# MegaD-328_7I7O_Shematic.net
KiCad netlist of a schematic drawn in Altium Designer
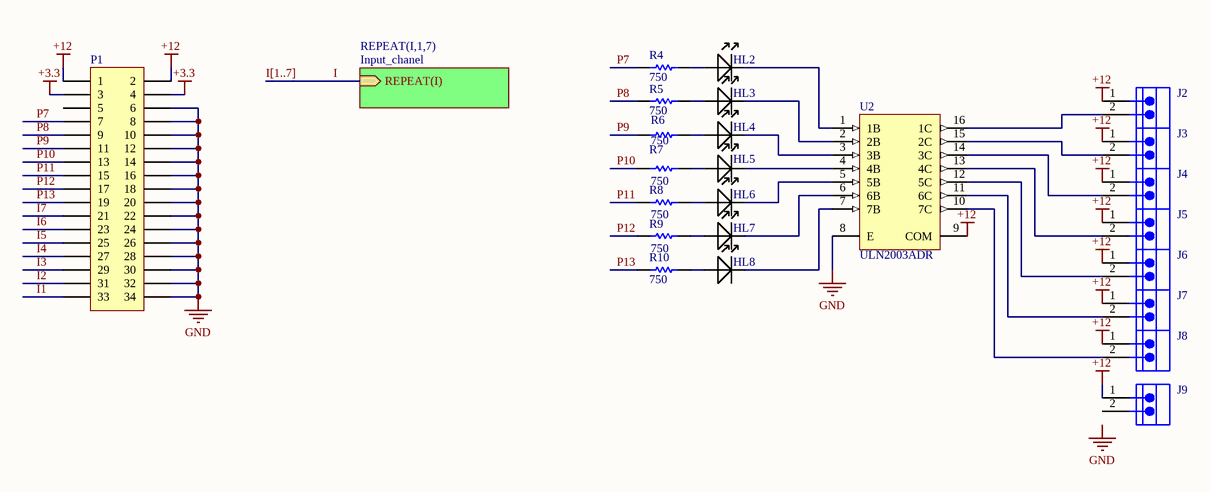
[diagram p0: MegaD-328_7I7O_Shematic.SchDoc]

(export (version "E")
  (design (tool "Eeschema 10.0.6"))
  (components
    (comp (ref "HL2")
      (value "LED_SMD")
      (footprint "0805_LED")
      (description "0805 led")
      (libsource (lib "altium-import") (part "root_0_LED_SMD_"))
    )
    (comp (ref "HL3")
      (value "LED_SMD")
      (footprint "0805_LED")
      (description "0805 led")
      (libsource (lib "altium-import") (part "root_0_LED_SMD_"))
    )
    (comp (ref "HL4")
      (value "LED_SMD")
      (footprint "0805_LED")
      (description "0805 led")
      (libsource (lib "altium-import") (part "root_0_LED_SMD_"))
    )
    (comp (ref "HL5")
      (value "LED_SMD")
      (footprint "0805_LED")
      (description "0805 led")
      (libsource (lib "altium-import") (part "root_0_LED_SMD_"))
    )
    (comp (ref "HL6")
      (value "LED_SMD")
      (footprint "0805_LED")
      (description "0805 led")
      (libsource (lib "altium-import") (part "root_0_LED_SMD_"))
    )
    (comp (ref "HL7")
      (value "LED_SMD")
      (footprint "0805_LED")
      (description "0805 led")
      (libsource (lib "altium-import") (part "root_0_LED_SMD_"))
    )
    (comp (ref "HL8")
      (value "LED_SMD")
      (footprint "0805_LED")
      (description "0805 led")
      (libsource (lib "altium-import") (part "root_0_LED_SMD_"))
    )
    (comp (ref "J2")
      (value "~")
      (footprint "DG301-5.0-02P-1X")
      (fields
        (field (name "MANUFACTURER") "Cixi KaiFeng")
        (field (name "PARTNUMBER") "KF120-02P-14")
        (field (name "CONTACT") "Brass")
      )
      (libsource (lib "altium-import") (part "root_3_Terminal_2_"))
    )
    (comp (ref "J3")
      (value "~")
      (footprint "DG301-5.0-02P-1X")
      (fields
        (field (name "MANUFACTURER") "Cixi KaiFeng")
        (field (name "PARTNUMBER") "KF120-02P-14")
        (field (name "CONTACT") "Brass")
      )
      (libsource (lib "altium-import") (part "root_3_Terminal_2_"))
    )
    (comp (ref "J4")
      (value "~")
      (footprint "DG301-5.0-02P-1X")
      (fields
        (field (name "MANUFACTURER") "Cixi KaiFeng")
        (field (name "PARTNUMBER") "KF120-02P-14")
        (field (name "CONTACT") "Brass")
      )
      (libsource (lib "altium-import") (part "root_3_Terminal_2_"))
    )
    (comp (ref "J5")
      (value "~")
      (footprint "DG301-5.0-02P-1X")
      (fields
        (field (name "MANUFACTURER") "Cixi KaiFeng")
        (field (name "PARTNUMBER") "KF120-02P-14")
        (field (name "CONTACT") "Brass")
      )
      (libsource (lib "altium-import") (part "root_3_Terminal_2_"))
    )
    (comp (ref "J6")
      (value "~")
      (footprint "DG301-5.0-02P-1X")
      (fields
        (field (name "MANUFACTURER") "Cixi KaiFeng")
        (field (name "PARTNUMBER") "KF120-02P-14")
        (field (name "CONTACT") "Brass")
      )
      (libsource (lib "altium-import") (part "root_3_Terminal_2_"))
    )
    (comp (ref "J7")
      (value "~")
      (footprint "DG301-5.0-02P-1X")
      (fields
        (field (name "MANUFACTURER") "Cixi KaiFeng")
        (field (name "PARTNUMBER") "KF120-02P-14")
        (field (name "CONTACT") "Brass")
      )
      (libsource (lib "altium-import") (part "root_3_Terminal_2_"))
    )
    (comp (ref "J8")
      (value "~")
      (footprint "DG301-5.0-02P-1X")
      (fields
        (field (name "MANUFACTURER") "Cixi KaiFeng")
        (field (name "PARTNUMBER") "KF120-02P-14")
        (field (name "CONTACT") "Brass")
      )
      (libsource (lib "altium-import") (part "root_3_Terminal_2_"))
    )
    (comp (ref "J9")
      (value "~")
      (footprint "DG301-5.0-02P-1X")
      (fields
        (field (name "MANUFACTURER") "Cixi KaiFeng")
        (field (name "PARTNUMBER") "KF120-02P-14")
        (field (name "CONTACT") "Brass")
      )
      (libsource (lib "altium-import") (part "root_3_Terminal_2_"))
    )
    (comp (ref "P1")
      (value "~")
      (footprint "HDR2X17-PLC")
      (description "Header, 17-Pin, Dual row")
      (fields (field (name "PUBLISHER") "Altium Limited"))
      (libsource (lib "web.skorpio") (part "Header 17X2"))
    )
    (comp (ref "R4")
      (value "RES_SMD")
      (footprint "RES0805")
      (fields (field (name "VAL") "750"))
      (libsource (lib "altium-import") (part "root_0_RES_SMD_"))
    )
    (comp (ref "R5")
      (value "RES_SMD")
      (footprint "RES0805")
      (fields (field (name "VAL") "750"))
      (libsource (lib "altium-import") (part "root_0_RES_SMD_"))
    )
    (comp (ref "R6")
      (value "RES_SMD")
      (footprint "RES0805")
      (fields (field (name "VAL") "750"))
      (libsource (lib "altium-import") (part "root_0_RES_SMD_"))
    )
    (comp (ref "R7")
      (value "RES_SMD")
      (footprint "RES0805")
      (fields (field (name "VAL") "750"))
      (libsource (lib "altium-import") (part "root_0_RES_SMD_"))
    )
    (comp (ref "R8")
      (value "RES_SMD")
      (footprint "RES0805")
      (fields (field (name "VAL") "750"))
      (libsource (lib "altium-import") (part "root_0_RES_SMD_"))
    )
    (comp (ref "R9")
      (value "RES_SMD")
      (footprint "RES0805")
      (fields (field (name "VAL") "750"))
      (libsource (lib "altium-import") (part "root_0_RES_SMD_"))
    )
    (comp (ref "R10")
      (value "RES_SMD")
      (footprint "RES0805")
      (fields (field (name "VAL") "750"))
      (libsource (lib "altium-import") (part "root_0_RES_SMD_"))
    )
    (comp (ref "U2")
      (value "ULN2003ADR")
      (footprint "SO-16_L")
      (fields (field (name "MANUFACTURER") "TexasInstruments"))
      (libsource (lib "altium-import") (part "root_0_ULN2003A_"))
    )
  )
  (nets
    (net (code "1") (name "+3.3") (class "Default")
      (node (ref "P1") (pin "3") (pinfunction "3_3") (pintype "passive"))
      (node (ref "P1") (pin "4") (pinfunction "4_4") (pintype "passive"))
    )
    (net (code "2") (name "+12") (class "Default")
      (node (ref "J2") (pin "1") (pinfunction "1_1") (pintype "passive"))
      (node (ref "J3") (pin "1") (pinfunction "1_1") (pintype "passive"))
      (node (ref "J4") (pin "1") (pinfunction "1_1") (pintype "passive"))
      (node (ref "J5") (pin "1") (pinfunction "1_1") (pintype "passive"))
      (node (ref "J6") (pin "1") (pinfunction "1_1") (pintype "passive"))
      (node (ref "J7") (pin "1") (pinfunction "1_1") (pintype "passive"))
      (node (ref "J8") (pin "1") (pinfunction "1_1") (pintype "passive"))
      (node (ref "J9") (pin "1") (pinfunction "1_1") (pintype "passive"))
      (node (ref "P1") (pin "1") (pinfunction "1_1") (pintype "passive"))
      (node (ref "P1") (pin "2") (pinfunction "2_2") (pintype "passive"))
      (node (ref "U2") (pin "9") (pinfunction "COM_9") (pintype "passive"))
    )
    (net (code "4") (name "/I1") (class "Default")
      (node (ref "P1") (pin "33") (pinfunction "33_33") (pintype "passive"))
    )
    (net (code "5") (name "/I2") (class "Default")
      (node (ref "P1") (pin "31") (pinfunction "31_31") (pintype "passive"))
    )
    (net (code "6") (name "/I3") (class "Default")
      (node (ref "P1") (pin "29") (pinfunction "29_29") (pintype "passive"))
    )
    (net (code "7") (name "/I4") (class "Default")
      (node (ref "P1") (pin "27") (pinfunction "27_27") (pintype "passive"))
    )
    (net (code "8") (name "/I5") (class "Default")
      (node (ref "P1") (pin "25") (pinfunction "25_25") (pintype "passive"))
    )
    (net (code "9") (name "/I6") (class "Default")
      (node (ref "P1") (pin "23") (pinfunction "23_23") (pintype "passive"))
    )
    (net (code "10") (name "/I7") (class "Default")
      (node (ref "P1") (pin "21") (pinfunction "21_21") (pintype "passive"))
    )
    (net (code "12") (name "/P7") (class "Default")
      (node (ref "P1") (pin "7") (pinfunction "7_7") (pintype "passive"))
      (node (ref "R4") (pin "1") (pinfunction "1_1") (pintype "passive"))
    )
    (net (code "13") (name "/P8") (class "Default")
      (node (ref "P1") (pin "9") (pinfunction "9_9") (pintype "passive"))
      (node (ref "R5") (pin "1") (pinfunction "1_1") (pintype "passive"))
    )
    (net (code "14") (name "/P9") (class "Default")
      (node (ref "P1") (pin "11") (pinfunction "11_11") (pintype "passive"))
      (node (ref "R6") (pin "1") (pinfunction "1_1") (pintype "passive"))
    )
    (net (code "15") (name "/P10") (class "Default")
      (node (ref "P1") (pin "13") (pinfunction "13_13") (pintype "passive"))
      (node (ref "R7") (pin "1") (pinfunction "1_1") (pintype "passive"))
    )
    (net (code "16") (name "/P11") (class "Default")
      (node (ref "P1") (pin "15") (pinfunction "15_15") (pintype "passive"))
      (node (ref "R8") (pin "1") (pinfunction "1_1") (pintype "passive"))
    )
    (net (code "17") (name "/P12") (class "Default")
      (node (ref "P1") (pin "17") (pinfunction "17_17") (pintype "passive"))
      (node (ref "R9") (pin "1") (pinfunction "1_1") (pintype "passive"))
    )
    (net (code "18") (name "/P13") (class "Default")
      (node (ref "P1") (pin "19") (pinfunction "19_19") (pintype "passive"))
      (node (ref "R10") (pin "1") (pinfunction "1_1") (pintype "passive"))
    )
    (net (code "19") (name "GND") (class "Default")
      (node (ref "P1") (pin "10") (pinfunction "10_10") (pintype "passive"))
      (node (ref "P1") (pin "12") (pinfunction "12_12") (pintype "passive"))
      (node (ref "P1") (pin "14") (pinfunction "14_14") (pintype "passive"))
      (node (ref "P1") (pin "16") (pinfunction "16_16") (pintype "passive"))
      (node (ref "P1") (pin "18") (pinfunction "18_18") (pintype "passive"))
      (node (ref "P1") (pin "20") (pinfunction "20_20") (pintype "passive"))
      (node (ref "P1") (pin "22") (pinfunction "22_22") (pintype "passive"))
      (node (ref "P1") (pin "24") (pinfunction "24_24") (pintype "passive"))
      (node (ref "P1") (pin "26") (pinfunction "26_26") (pintype "passive"))
      (node (ref "P1") (pin "28") (pinfunction "28_28") (pintype "passive"))
      (node (ref "P1") (pin "30") (pinfunction "30_30") (pintype "passive"))
      (node (ref "P1") (pin "32") (pinfunction "32_32") (pintype "passive"))
      (node (ref "P1") (pin "34") (pinfunction "34_34") (pintype "passive"))
      (node (ref "P1") (pin "6") (pinfunction "6_6") (pintype "passive"))
      (node (ref "P1") (pin "8") (pinfunction "8_8") (pintype "passive"))
      (node (ref "U2") (pin "8") (pinfunction "E_8") (pintype "passive"))
    )
    (net (code "20") (name "Net-(HL2-anode)") (class "Default")
      (node (ref "HL2") (pin "1") (pinfunction "anode_1") (pintype "passive"))
      (node (ref "R4") (pin "2") (pinfunction "2_2") (pintype "passive"))
    )
    (net (code "21") (name "Net-(HL2-cathode)") (class "Default")
      (node (ref "HL2") (pin "2") (pinfunction "cathode_2") (pintype "passive"))
      (node (ref "U2") (pin "1") (pinfunction "1B_1") (pintype "input"))
    )
    (net (code "22") (name "Net-(HL3-anode)") (class "Default")
      (node (ref "HL3") (pin "1") (pinfunction "anode_1") (pintype "passive"))
      (node (ref "R5") (pin "2") (pinfunction "2_2") (pintype "passive"))
    )
    (net (code "23") (name "Net-(HL3-cathode)") (class "Default")
      (node (ref "HL3") (pin "2") (pinfunction "cathode_2") (pintype "passive"))
      (node (ref "U2") (pin "2") (pinfunction "2B_2") (pintype "input"))
    )
    (net (code "24") (name "Net-(HL4-anode)") (class "Default")
      (node (ref "HL4") (pin "1") (pinfunction "anode_1") (pintype "passive"))
      (node (ref "R6") (pin "2") (pinfunction "2_2") (pintype "passive"))
    )
    (net (code "25") (name "Net-(HL4-cathode)") (class "Default")
      (node (ref "HL4") (pin "2") (pinfunction "cathode_2") (pintype "passive"))
      (node (ref "U2") (pin "3") (pinfunction "3B_3") (pintype "input"))
    )
    (net (code "26") (name "Net-(HL5-anode)") (class "Default")
      (node (ref "HL5") (pin "1") (pinfunction "anode_1") (pintype "passive"))
      (node (ref "R7") (pin "2") (pinfunction "2_2") (pintype "passive"))
    )
    (net (code "27") (name "Net-(HL5-cathode)") (class "Default")
      (node (ref "HL5") (pin "2") (pinfunction "cathode_2") (pintype "passive"))
      (node (ref "U2") (pin "4") (pinfunction "4B_4") (pintype "input"))
    )
    (net (code "28") (name "Net-(HL6-anode)") (class "Default")
      (node (ref "HL6") (pin "1") (pinfunction "anode_1") (pintype "passive"))
      (node (ref "R8") (pin "2") (pinfunction "2_2") (pintype "passive"))
    )
    (net (code "29") (name "Net-(HL6-cathode)") (class "Default")
      (node (ref "HL6") (pin "2") (pinfunction "cathode_2") (pintype "passive"))
      (node (ref "U2") (pin "5") (pinfunction "5B_5") (pintype "input"))
    )
    (net (code "30") (name "Net-(HL7-anode)") (class "Default")
      (node (ref "HL7") (pin "1") (pinfunction "anode_1") (pintype "passive"))
      (node (ref "R9") (pin "2") (pinfunction "2_2") (pintype "passive"))
    )
    (net (code "31") (name "Net-(HL7-cathode)") (class "Default")
      (node (ref "HL7") (pin "2") (pinfunction "cathode_2") (pintype "passive"))
      (node (ref "U2") (pin "6") (pinfunction "6B_6") (pintype "input"))
    )
    (net (code "32") (name "Net-(HL8-anode)") (class "Default")
      (node (ref "HL8") (pin "1") (pinfunction "anode_1") (pintype "passive"))
      (node (ref "R10") (pin "2") (pinfunction "2_2") (pintype "passive"))
    )
    (net (code "33") (name "Net-(HL8-cathode)") (class "Default")
      (node (ref "HL8") (pin "2") (pinfunction "cathode_2") (pintype "passive"))
      (node (ref "U2") (pin "7") (pinfunction "7B_7") (pintype "input"))
    )
    (net (code "34") (name "Net-(U2-1C)") (class "Default")
      (node (ref "J2") (pin "2") (pinfunction "2_2") (pintype "passive"))
      (node (ref "U2") (pin "16") (pinfunction "1C_16") (pintype "output"))
    )
    (net (code "35") (name "Net-(U2-2C)") (class "Default")
      (node (ref "J3") (pin "2") (pinfunction "2_2") (pintype "passive"))
      (node (ref "U2") (pin "15") (pinfunction "2C_15") (pintype "output"))
    )
    (net (code "36") (name "Net-(U2-3C)") (class "Default")
      (node (ref "J4") (pin "2") (pinfunction "2_2") (pintype "passive"))
      (node (ref "U2") (pin "14") (pinfunction "3C_14") (pintype "output"))
    )
    (net (code "37") (name "Net-(U2-4C)") (class "Default")
      (node (ref "J5") (pin "2") (pinfunction "2_2") (pintype "passive"))
      (node (ref "U2") (pin "13") (pinfunction "4C_13") (pintype "output"))
    )
    (net (code "38") (name "Net-(U2-5C)") (class "Default")
      (node (ref "J6") (pin "2") (pinfunction "2_2") (pintype "passive"))
      (node (ref "U2") (pin "12") (pinfunction "5C_12") (pintype "output"))
    )
    (net (code "39") (name "Net-(U2-6C)") (class "Default")
      (node (ref "J7") (pin "2") (pinfunction "2_2") (pintype "passive"))
      (node (ref "U2") (pin "11") (pinfunction "6C_11") (pintype "output"))
    )
    (net (code "40") (name "Net-(U2-7C)") (class "Default")
      (node (ref "J8") (pin "2") (pinfunction "2_2") (pintype "passive"))
      (node (ref "U2") (pin "10") (pinfunction "7C_10") (pintype "output"))
    )
    (net (code "41") (name "unconnected-(J9-Pad2)") (class "Default")
      (node (ref "J9") (pin "2") (pinfunction "2_2") (pintype "passive"))
    )
    (net (code "42") (name "unconnected-(P1-Pad5)") (class "Default")
      (node (ref "P1") (pin "5") (pinfunction "5_5") (pintype "passive"))
    )
  )
)
